# Instigator2012ConnectorSch.net
KiCad netlist of a schematic drawn in Altium Designer
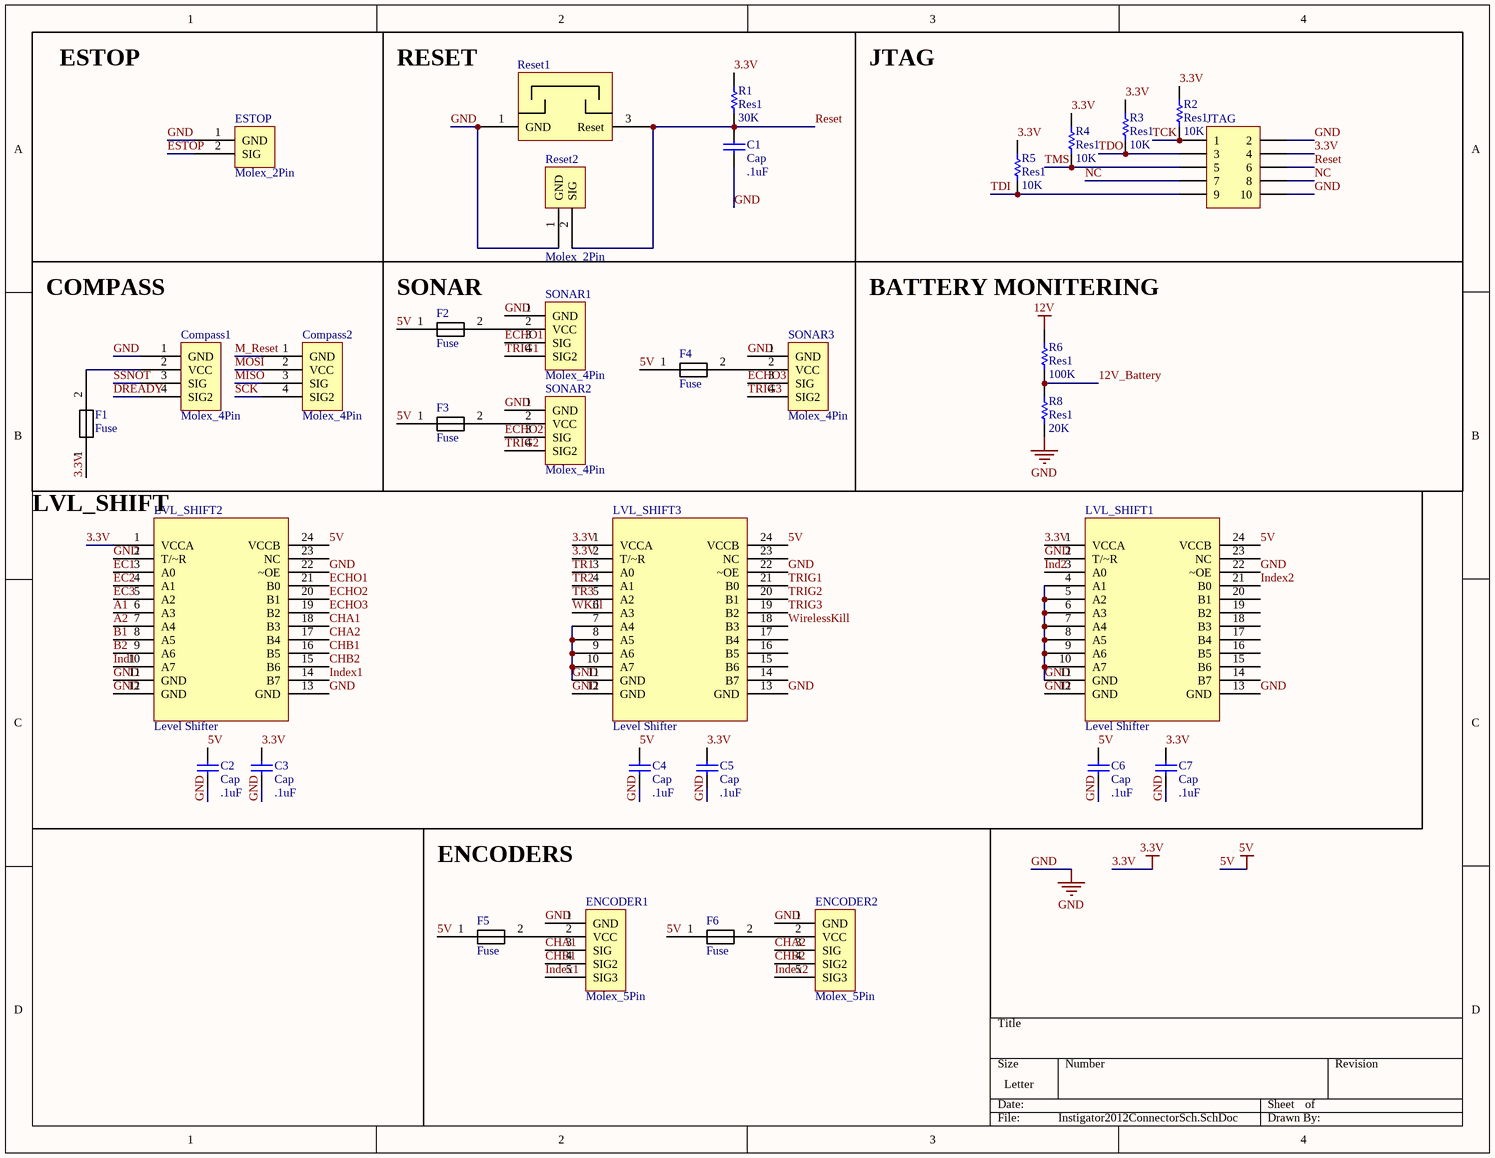
[diagram p0: Instigator2012ConnectorSch.SchDoc]

(export (version "E")
  (design (tool "Eeschema 10.0.6"))
  (components
    (comp (ref "C1")
      (value "Cap")
      (footprint "1608[0603]")
      (description "Capacitor")
      (fields (field (name "ALTIUM_VALUE") ".1uF") (field (name "PUBLISHER") "Altium Limited"))
      (libsource (lib "Miscellaneous Devices") (part "Cap"))
    )
    (comp (ref "C2")
      (value "Cap")
      (footprint "1608[0603]")
      (description "Capacitor")
      (fields (field (name "ALTIUM_VALUE") ".1uF") (field (name "PUBLISHER") "Altium Limited"))
      (libsource (lib "Miscellaneous Devices") (part "Cap"))
    )
    (comp (ref "C3")
      (value "Cap")
      (footprint "1608[0603]")
      (description "Capacitor")
      (fields (field (name "ALTIUM_VALUE") ".1uF") (field (name "PUBLISHER") "Altium Limited"))
      (libsource (lib "Miscellaneous Devices") (part "Cap"))
    )
    (comp (ref "C4")
      (value "Cap")
      (footprint "1608[0603]")
      (description "Capacitor")
      (fields (field (name "ALTIUM_VALUE") ".1uF") (field (name "PUBLISHER") "Altium Limited"))
      (libsource (lib "Miscellaneous Devices") (part "Cap"))
    )
    (comp (ref "C5")
      (value "Cap")
      (footprint "1608[0603]")
      (description "Capacitor")
      (fields (field (name "ALTIUM_VALUE") ".1uF") (field (name "PUBLISHER") "Altium Limited"))
      (libsource (lib "Miscellaneous Devices") (part "Cap"))
    )
    (comp (ref "C6")
      (value "Cap")
      (footprint "1608[0603]")
      (description "Capacitor")
      (fields (field (name "ALTIUM_VALUE") ".1uF") (field (name "PUBLISHER") "Altium Limited"))
      (libsource (lib "Miscellaneous Devices") (part "Cap"))
    )
    (comp (ref "C7")
      (value "Cap")
      (footprint "1608[0603]")
      (description "Capacitor")
      (fields (field (name "ALTIUM_VALUE") ".1uF") (field (name "PUBLISHER") "Altium Limited"))
      (libsource (lib "Miscellaneous Devices") (part "Cap"))
    )
    (comp (ref "Compass1")
      (value "Molex_4Pin")
      (footprint "PCBComponent_1")
      (libsource (lib "Molex_4Pin") (part "Molex_4Pin"))
    )
    (comp (ref "Compass2")
      (value "Molex_4Pin")
      (footprint "PCBComponent_1")
      (libsource (lib "Molex_4Pin") (part "Molex_4Pin"))
    )
    (comp (ref "ENCODER1")
      (value "Molex_5Pin")
      (footprint "PCBComponent_1")
      (libsource (lib "Molex_5Pin") (part "Molex_5Pin"))
    )
    (comp (ref "ENCODER2")
      (value "Molex_5Pin")
      (footprint "PCBComponent_1")
      (libsource (lib "Molex_5Pin") (part "Molex_5Pin"))
    )
    (comp (ref "ESTOP")
      (value "Molex_2Pin")
      (footprint "PCBComponent_1")
      (libsource (lib "") (part "Molex_2Pin_1"))
    )
    (comp (ref "F1")
      (value "Fuse")
      (footprint "PCBComponent_1 - duplicate")
      (libsource (lib "VPOL5A_PowerRegulator") (part "Fuse"))
    )
    (comp (ref "F2")
      (value "Fuse")
      (footprint "PCBComponent_1 - duplicate")
      (libsource (lib "VPOL5A_PowerRegulator") (part "Fuse"))
    )
    (comp (ref "F3")
      (value "Fuse")
      (footprint "PCBComponent_1 - duplicate")
      (libsource (lib "VPOL5A_PowerRegulator") (part "Fuse"))
    )
    (comp (ref "F4")
      (value "Fuse")
      (footprint "PCBComponent_1 - duplicate")
      (libsource (lib "VPOL5A_PowerRegulator") (part "Fuse"))
    )
    (comp (ref "F5")
      (value "Fuse")
      (footprint "PCBComponent_1 - duplicate")
      (libsource (lib "VPOL5A_PowerRegulator") (part "Fuse"))
    )
    (comp (ref "F6")
      (value "Fuse")
      (footprint "PCBComponent_1 - duplicate")
      (libsource (lib "VPOL5A_PowerRegulator") (part "Fuse"))
    )
    (comp (ref "JTAG")
      (value "Header 5X2")
      (footprint "HDR2X5")
      (description "Header, 5-Pin, Dual row")
      (fields (field (name "PUBLISHER") "Altium Limited"))
      (libsource (lib "Miscellaneous Connectors") (part "Header 5X2"))
    )
    (comp (ref "LVL_SHIFT1")
      (value "Level Shifter")
      (footprint "TSOP65P640X110-24N")
      (libsource (lib "LevelShifter_FairchildSemi") (part "Level Shifter"))
    )
    (comp (ref "LVL_SHIFT2")
      (value "Level Shifter")
      (footprint "TSOP65P640X110-24N")
      (libsource (lib "LevelShifter_FairchildSemi") (part "Level Shifter"))
    )
    (comp (ref "LVL_SHIFT3")
      (value "Level Shifter")
      (footprint "TSOP65P640X110-24N")
      (libsource (lib "LevelShifter_FairchildSemi") (part "Level Shifter"))
    )
    (comp (ref "R1")
      (value "Res1")
      (footprint "1608[0603]")
      (description "Resistor")
      (fields (field (name "ALTIUM_VALUE") "30K") (field (name "PUBLISHER") "Altium Limited"))
      (libsource (lib "Miscellaneous Devices") (part "Res1"))
    )
    (comp (ref "R2")
      (value "Res1")
      (footprint "1608[0603]")
      (description "Resistor")
      (fields (field (name "ALTIUM_VALUE") "10K") (field (name "PUBLISHER") "Altium Limited"))
      (libsource (lib "Miscellaneous Devices") (part "Res1"))
    )
    (comp (ref "R3")
      (value "Res1")
      (footprint "1608[0603]")
      (description "Resistor")
      (fields (field (name "ALTIUM_VALUE") "10K") (field (name "PUBLISHER") "Altium Limited"))
      (libsource (lib "Miscellaneous Devices") (part "Res1"))
    )
    (comp (ref "R4")
      (value "Res1")
      (footprint "1608[0603]")
      (description "Resistor")
      (fields (field (name "ALTIUM_VALUE") "10K") (field (name "PUBLISHER") "Altium Limited"))
      (libsource (lib "Miscellaneous Devices") (part "Res1"))
    )
    (comp (ref "R5")
      (value "Res1")
      (footprint "1608[0603]")
      (description "Resistor")
      (fields (field (name "ALTIUM_VALUE") "10K") (field (name "PUBLISHER") "Altium Limited"))
      (libsource (lib "Miscellaneous Devices") (part "Res1"))
    )
    (comp (ref "R6")
      (value "Res1")
      (footprint "1608[0603]")
      (description "Resistor")
      (fields (field (name "ALTIUM_VALUE") "100K") (field (name "PUBLISHER") "Altium Limited"))
      (libsource (lib "Miscellaneous Devices") (part "Res1"))
    )
    (comp (ref "R8")
      (value "Res1")
      (footprint "1608[0603]")
      (description "Resistor")
      (fields (field (name "ALTIUM_VALUE") "20K") (field (name "PUBLISHER") "Altium Limited"))
      (libsource (lib "Miscellaneous Devices") (part "Res1"))
    )
    (comp (ref "Reset1")
      (value "l")
      (footprint "PCBComponent_1")
      (libsource (lib "PushButton_Reset") (part "Component_1"))
    )
    (comp (ref "Reset2")
      (value "Molex_2Pin")
      (footprint "PCBComponent_1")
      (libsource (lib "Molex_2Pin") (part "Molex_2Pin"))
    )
    (comp (ref "SONAR1")
      (value "Molex_4Pin")
      (footprint "PCBComponent_1")
      (libsource (lib "Molex_4Pin") (part "Molex_4Pin"))
    )
    (comp (ref "SONAR2")
      (value "Molex_4Pin")
      (footprint "PCBComponent_1")
      (libsource (lib "Molex_4Pin") (part "Molex_4Pin"))
    )
    (comp (ref "SONAR3")
      (value "Molex_4Pin")
      (footprint "PCBComponent_1")
      (libsource (lib "Molex_4Pin") (part "Molex_4Pin"))
    )
  )
  (nets
    (net (code "1") (name "/12V_Battery") (class "Default")
      (node (ref "R6") (pin "1") (pinfunction "1_1") (pintype "passive"))
      (node (ref "R8") (pin "2") (pinfunction "2_2") (pintype "passive"))
    )
    (net (code "2") (name "/A1") (class "Default")
      (node (ref "LVL_SHIFT2") (pin "6") (pinfunction "A3_6") (pintype "passive"))
    )
    (net (code "3") (name "/A2") (class "Default")
      (node (ref "LVL_SHIFT2") (pin "7") (pinfunction "A4_7") (pintype "passive"))
    )
    (net (code "4") (name "/B1") (class "Default")
      (node (ref "LVL_SHIFT2") (pin "8") (pinfunction "A5_8") (pintype "passive"))
    )
    (net (code "5") (name "/B2") (class "Default")
      (node (ref "LVL_SHIFT2") (pin "9") (pinfunction "A6_9") (pintype "passive"))
    )
    (net (code "6") (name "/CHA1") (class "Default")
      (node (ref "ENCODER1") (pin "3") (pinfunction "SIG_3") (pintype "power_in"))
      (node (ref "LVL_SHIFT2") (pin "18") (pinfunction "B3_18") (pintype "passive"))
    )
    (net (code "7") (name "/CHA2") (class "Default")
      (node (ref "ENCODER2") (pin "3") (pinfunction "SIG_3") (pintype "power_in"))
      (node (ref "LVL_SHIFT2") (pin "17") (pinfunction "B4_17") (pintype "passive"))
    )
    (net (code "8") (name "/CHB1") (class "Default")
      (node (ref "ENCODER1") (pin "4") (pinfunction "SIG2_4") (pintype "power_in"))
      (node (ref "LVL_SHIFT2") (pin "16") (pinfunction "B5_16") (pintype "passive"))
    )
    (net (code "9") (name "/CHB2") (class "Default")
      (node (ref "ENCODER2") (pin "4") (pinfunction "SIG2_4") (pintype "power_in"))
      (node (ref "LVL_SHIFT2") (pin "15") (pinfunction "B6_15") (pintype "passive"))
    )
    (net (code "10") (name "/DREADY") (class "Default")
      (node (ref "Compass1") (pin "4") (pinfunction "SIG2_4") (pintype "power_in"))
    )
    (net (code "11") (name "/EC1") (class "Default")
      (node (ref "LVL_SHIFT2") (pin "3") (pinfunction "A0_3") (pintype "passive"))
    )
    (net (code "12") (name "/EC2") (class "Default")
      (node (ref "LVL_SHIFT2") (pin "4") (pinfunction "A1_4") (pintype "passive"))
    )
    (net (code "13") (name "/EC3") (class "Default")
      (node (ref "LVL_SHIFT2") (pin "5") (pinfunction "A2_5") (pintype "passive"))
    )
    (net (code "14") (name "/ECHO1") (class "Default")
      (node (ref "LVL_SHIFT2") (pin "21") (pinfunction "B0_21") (pintype "passive"))
      (node (ref "SONAR1") (pin "3") (pinfunction "SIG_3") (pintype "power_in"))
    )
    (net (code "15") (name "/ECHO2") (class "Default")
      (node (ref "LVL_SHIFT2") (pin "20") (pinfunction "B1_20") (pintype "passive"))
      (node (ref "SONAR2") (pin "3") (pinfunction "SIG_3") (pintype "power_in"))
    )
    (net (code "16") (name "/ECHO3") (class "Default")
      (node (ref "LVL_SHIFT2") (pin "19") (pinfunction "B2_19") (pintype "passive"))
      (node (ref "SONAR3") (pin "3") (pinfunction "SIG_3") (pintype "power_in"))
    )
    (net (code "17") (name "/ESTOP") (class "Default")
      (node (ref "ESTOP") (pin "2") (pinfunction "SIG_2") (pintype "passive"))
    )
    (net (code "18") (name "/Ind1") (class "Default")
      (node (ref "LVL_SHIFT2") (pin "10") (pinfunction "A7_10") (pintype "passive"))
    )
    (net (code "19") (name "/Ind2") (class "Default")
      (node (ref "LVL_SHIFT1") (pin "3") (pinfunction "A0_3") (pintype "passive"))
    )
    (net (code "20") (name "/Index1") (class "Default")
      (node (ref "ENCODER1") (pin "5") (pinfunction "SIG3_5") (pintype "power_in"))
      (node (ref "LVL_SHIFT2") (pin "14") (pinfunction "B7_14") (pintype "passive"))
    )
    (net (code "21") (name "/Index2") (class "Default")
      (node (ref "ENCODER2") (pin "5") (pinfunction "SIG3_5") (pintype "power_in"))
      (node (ref "LVL_SHIFT1") (pin "21") (pinfunction "B0_21") (pintype "passive"))
    )
    (net (code "22") (name "/MISO") (class "Default")
      (node (ref "Compass2") (pin "3") (pinfunction "SIG_3") (pintype "power_in"))
    )
    (net (code "23") (name "/MOSI") (class "Default")
      (node (ref "Compass2") (pin "2") (pinfunction "VCC_2") (pintype "power_in"))
    )
    (net (code "24") (name "/M_Reset") (class "Default")
      (node (ref "Compass2") (pin "1") (pinfunction "GND_1") (pintype "power_in"))
    )
    (net (code "25") (name "/NC") (class "Default")
      (node (ref "JTAG") (pin "7") (pinfunction "7_7") (pintype "passive"))
      (node (ref "JTAG") (pin "8") (pinfunction "8_8") (pintype "passive"))
    )
    (net (code "26") (name "/Reset") (class "Default")
      (node (ref "C1") (pin "2") (pinfunction "2_2") (pintype "passive"))
      (node (ref "JTAG") (pin "6") (pinfunction "6_6") (pintype "passive"))
      (node (ref "R1") (pin "1") (pinfunction "1_1") (pintype "passive"))
      (node (ref "Reset1") (pin "3") (pinfunction "Reset_3") (pintype "passive"))
      (node (ref "Reset2") (pin "2") (pinfunction "SIG_2") (pintype "passive"))
    )
    (net (code "27") (name "/SCK") (class "Default")
      (node (ref "Compass2") (pin "4") (pinfunction "SIG2_4") (pintype "power_in"))
    )
    (net (code "28") (name "/SSNOT") (class "Default")
      (node (ref "Compass1") (pin "3") (pinfunction "SIG_3") (pintype "power_in"))
    )
    (net (code "29") (name "/TCK") (class "Default")
      (node (ref "JTAG") (pin "1") (pinfunction "1_1") (pintype "passive"))
      (node (ref "R2") (pin "1") (pinfunction "1_1") (pintype "passive"))
    )
    (net (code "30") (name "/TDI") (class "Default")
      (node (ref "JTAG") (pin "9") (pinfunction "9_9") (pintype "passive"))
      (node (ref "R5") (pin "1") (pinfunction "1_1") (pintype "passive"))
    )
    (net (code "31") (name "/TDO") (class "Default")
      (node (ref "JTAG") (pin "3") (pinfunction "3_3") (pintype "passive"))
      (node (ref "R3") (pin "1") (pinfunction "1_1") (pintype "passive"))
    )
    (net (code "32") (name "/TMS") (class "Default")
      (node (ref "JTAG") (pin "5") (pinfunction "5_5") (pintype "passive"))
      (node (ref "R4") (pin "1") (pinfunction "1_1") (pintype "passive"))
    )
    (net (code "33") (name "/TR1") (class "Default")
      (node (ref "LVL_SHIFT3") (pin "3") (pinfunction "A0_3") (pintype "passive"))
    )
    (net (code "34") (name "/TR2") (class "Default")
      (node (ref "LVL_SHIFT3") (pin "4") (pinfunction "A1_4") (pintype "passive"))
    )
    (net (code "35") (name "/TR3") (class "Default")
      (node (ref "LVL_SHIFT3") (pin "5") (pinfunction "A2_5") (pintype "passive"))
    )
    (net (code "36") (name "/TRIG1") (class "Default")
      (node (ref "LVL_SHIFT3") (pin "21") (pinfunction "B0_21") (pintype "passive"))
      (node (ref "SONAR1") (pin "4") (pinfunction "SIG2_4") (pintype "power_in"))
    )
    (net (code "37") (name "/TRIG2") (class "Default")
      (node (ref "LVL_SHIFT3") (pin "20") (pinfunction "B1_20") (pintype "passive"))
      (node (ref "SONAR2") (pin "4") (pinfunction "SIG2_4") (pintype "power_in"))
    )
    (net (code "38") (name "/TRIG3") (class "Default")
      (node (ref "LVL_SHIFT3") (pin "19") (pinfunction "B2_19") (pintype "passive"))
      (node (ref "SONAR3") (pin "4") (pinfunction "SIG2_4") (pintype "power_in"))
    )
    (net (code "39") (name "/WKill") (class "Default")
      (node (ref "LVL_SHIFT3") (pin "6") (pinfunction "A3_6") (pintype "passive"))
    )
    (net (code "40") (name "/WirelessKill") (class "Default")
      (node (ref "LVL_SHIFT3") (pin "18") (pinfunction "B3_18") (pintype "passive"))
    )
    (net (code "41") (name "3.3V") (class "Default")
      (node (ref "C3") (pin "2") (pinfunction "2_2") (pintype "passive"))
      (node (ref "C5") (pin "2") (pinfunction "2_2") (pintype "passive"))
      (node (ref "C7") (pin "2") (pinfunction "2_2") (pintype "passive"))
      (node (ref "F1") (pin "1") (pintype "passive"))
      (node (ref "JTAG") (pin "4") (pinfunction "4_4") (pintype "passive"))
      (node (ref "LVL_SHIFT1") (pin "1") (pinfunction "VCCA_1") (pintype "power_in"))
      (node (ref "LVL_SHIFT2") (pin "1") (pinfunction "VCCA_1") (pintype "power_in"))
      (node (ref "LVL_SHIFT3") (pin "1") (pinfunction "VCCA_1") (pintype "power_in"))
      (node (ref "LVL_SHIFT3") (pin "2") (pinfunction "T/~R_2") (pintype "passive"))
      (node (ref "R1") (pin "2") (pinfunction "2_2") (pintype "passive"))
      (node (ref "R2") (pin "2") (pinfunction "2_2") (pintype "passive"))
      (node (ref "R3") (pin "2") (pinfunction "2_2") (pintype "passive"))
      (node (ref "R4") (pin "2") (pinfunction "2_2") (pintype "passive"))
      (node (ref "R5") (pin "2") (pinfunction "2_2") (pintype "passive"))
    )
    (net (code "42") (name "5V") (class "Default")
      (node (ref "C2") (pin "2") (pinfunction "2_2") (pintype "passive"))
      (node (ref "C4") (pin "2") (pinfunction "2_2") (pintype "passive"))
      (node (ref "C6") (pin "2") (pinfunction "2_2") (pintype "passive"))
      (node (ref "F2") (pin "1") (pintype "passive"))
      (node (ref "F3") (pin "1") (pintype "passive"))
      (node (ref "F4") (pin "1") (pintype "passive"))
      (node (ref "F5") (pin "1") (pintype "passive"))
      (node (ref "F6") (pin "1") (pintype "passive"))
      (node (ref "LVL_SHIFT1") (pin "24") (pinfunction "VCCB_24") (pintype "passive"))
      (node (ref "LVL_SHIFT2") (pin "24") (pinfunction "VCCB_24") (pintype "passive"))
      (node (ref "LVL_SHIFT3") (pin "24") (pinfunction "VCCB_24") (pintype "passive"))
    )
    (net (code "43") (name "12V") (class "Default")
      (node (ref "R6") (pin "2") (pinfunction "2_2") (pintype "passive"))
    )
    (net (code "44") (name "GND") (class "Default")
      (node (ref "C1") (pin "1") (pinfunction "1_1") (pintype "passive"))
      (node (ref "C2") (pin "1") (pinfunction "1_1") (pintype "passive"))
      (node (ref "C3") (pin "1") (pinfunction "1_1") (pintype "passive"))
      (node (ref "C4") (pin "1") (pinfunction "1_1") (pintype "passive"))
      (node (ref "C5") (pin "1") (pinfunction "1_1") (pintype "passive"))
      (node (ref "C6") (pin "1") (pinfunction "1_1") (pintype "passive"))
      (node (ref "C7") (pin "1") (pinfunction "1_1") (pintype "passive"))
      (node (ref "Compass1") (pin "1") (pinfunction "GND_1") (pintype "power_in"))
      (node (ref "ENCODER1") (pin "1") (pinfunction "GND_1") (pintype "power_in"))
      (node (ref "ENCODER2") (pin "1") (pinfunction "GND_1") (pintype "power_in"))
      (node (ref "ESTOP") (pin "1") (pinfunction "GND_1") (pintype "power_in"))
      (node (ref "JTAG") (pin "10") (pinfunction "10_10") (pintype "passive"))
      (node (ref "JTAG") (pin "2") (pinfunction "2_2") (pintype "passive"))
      (node (ref "LVL_SHIFT1") (pin "10") (pinfunction "A7_10") (pintype "passive"))
      (node (ref "LVL_SHIFT1") (pin "11") (pinfunction "GND_11") (pintype "passive"))
      (node (ref "LVL_SHIFT1") (pin "12") (pinfunction "GND_12") (pintype "passive"))
      (node (ref "LVL_SHIFT1") (pin "13") (pinfunction "GND_13") (pintype "passive"))
      (node (ref "LVL_SHIFT1") (pin "2") (pinfunction "T/~R_2") (pintype "passive"))
      (node (ref "LVL_SHIFT1") (pin "22") (pinfunction "~OE_22") (pintype "passive"))
      (node (ref "LVL_SHIFT1") (pin "4") (pinfunction "A1_4") (pintype "passive"))
      (node (ref "LVL_SHIFT1") (pin "5") (pinfunction "A2_5") (pintype "passive"))
      (node (ref "LVL_SHIFT1") (pin "6") (pinfunction "A3_6") (pintype "passive"))
      (node (ref "LVL_SHIFT1") (pin "7") (pinfunction "A4_7") (pintype "passive"))
      (node (ref "LVL_SHIFT1") (pin "8") (pinfunction "A5_8") (pintype "passive"))
      (node (ref "LVL_SHIFT1") (pin "9") (pinfunction "A6_9") (pintype "passive"))
      (node (ref "LVL_SHIFT2") (pin "11") (pinfunction "GND_11") (pintype "passive"))
      (node (ref "LVL_SHIFT2") (pin "12") (pinfunction "GND_12") (pintype "passive"))
      (node (ref "LVL_SHIFT2") (pin "13") (pinfunction "GND_13") (pintype "passive"))
      (node (ref "LVL_SHIFT2") (pin "2") (pinfunction "T/~R_2") (pintype "passive"))
      (node (ref "LVL_SHIFT2") (pin "22") (pinfunction "~OE_22") (pintype "passive"))
      (node (ref "LVL_SHIFT3") (pin "10") (pinfunction "A7_10") (pintype "passive"))
      (node (ref "LVL_SHIFT3") (pin "11") (pinfunction "GND_11") (pintype "passive"))
      (node (ref "LVL_SHIFT3") (pin "12") (pinfunction "GND_12") (pintype "passive"))
      (node (ref "LVL_SHIFT3") (pin "13") (pinfunction "GND_13") (pintype "passive"))
      (node (ref "LVL_SHIFT3") (pin "22") (pinfunction "~OE_22") (pintype "passive"))
      (node (ref "LVL_SHIFT3") (pin "7") (pinfunction "A4_7") (pintype "passive"))
      (node (ref "LVL_SHIFT3") (pin "8") (pinfunction "A5_8") (pintype "passive"))
      (node (ref "LVL_SHIFT3") (pin "9") (pinfunction "A6_9") (pintype "passive"))
      (node (ref "R8") (pin "1") (pinfunction "1_1") (pintype "passive"))
      (node (ref "Reset1") (pin "1") (pinfunction "GND_1") (pintype "power_in"))
      (node (ref "Reset2") (pin "1") (pinfunction "GND_1") (pintype "power_in"))
      (node (ref "SONAR1") (pin "1") (pinfunction "GND_1") (pintype "power_in"))
      (node (ref "SONAR2") (pin "1") (pinfunction "GND_1") (pintype "power_in"))
      (node (ref "SONAR3") (pin "1") (pinfunction "GND_1") (pintype "power_in"))
    )
    (net (code "45") (name "Net-(Compass1-VCC)") (class "Default")
      (node (ref "Compass1") (pin "2") (pinfunction "VCC_2") (pintype "power_in"))
      (node (ref "F1") (pin "2") (pintype "passive"))
    )
    (net (code "46") (name "Net-(ENCODER1-VCC)") (class "Default")
      (node (ref "ENCODER1") (pin "2") (pinfunction "VCC_2") (pintype "power_in"))
      (node (ref "F5") (pin "2") (pintype "passive"))
    )
    (net (code "47") (name "Net-(ENCODER2-VCC)") (class "Default")
      (node (ref "ENCODER2") (pin "2") (pinfunction "VCC_2") (pintype "power_in"))
      (node (ref "F6") (pin "2") (pintype "passive"))
    )
    (net (code "48") (name "Net-(SONAR1-VCC)") (class "Default")
      (node (ref "F2") (pin "2") (pintype "passive"))
      (node (ref "SONAR1") (pin "2") (pinfunction "VCC_2") (pintype "power_in"))
    )
    (net (code "49") (name "Net-(SONAR2-VCC)") (class "Default")
      (node (ref "F3") (pin "2") (pintype "passive"))
      (node (ref "SONAR2") (pin "2") (pinfunction "VCC_2") (pintype "power_in"))
    )
    (net (code "50") (name "Net-(SONAR3-VCC)") (class "Default")
      (node (ref "F4") (pin "2") (pintype "passive"))
      (node (ref "SONAR3") (pin "2") (pinfunction "VCC_2") (pintype "power_in"))
    )
    (net (code "51") (name "unconnected-(LVL_SHIFT1-B1-Pad20)") (class "Default")
      (node (ref "LVL_SHIFT1") (pin "20") (pinfunction "B1_20") (pintype "passive"))
    )
    (net (code "52") (name "unconnected-(LVL_SHIFT1-B2-Pad19)") (class "Default")
      (node (ref "LVL_SHIFT1") (pin "19") (pinfunction "B2_19") (pintype "passive"))
    )
    (net (code "53") (name "unconnected-(LVL_SHIFT1-B3-Pad18)") (class "Default")
      (node (ref "LVL_SHIFT1") (pin "18") (pinfunction "B3_18") (pintype "passive"))
    )
    (net (code "54") (name "unconnected-(LVL_SHIFT1-B4-Pad17)") (class "Default")
      (node (ref "LVL_SHIFT1") (pin "17") (pinfunction "B4_17") (pintype "passive"))
    )
    (net (code "55") (name "unconnected-(LVL_SHIFT1-B5-Pad16)") (class "Default")
      (node (ref "LVL_SHIFT1") (pin "16") (pinfunction "B5_16") (pintype "passive"))
    )
    (net (code "56") (name "unconnected-(LVL_SHIFT1-B6-Pad15)") (class "Default")
      (node (ref "LVL_SHIFT1") (pin "15") (pinfunction "B6_15") (pintype "passive"))
    )
    (net (code "57") (name "unconnected-(LVL_SHIFT1-B7-Pad14)") (class "Default")
      (node (ref "LVL_SHIFT1") (pin "14") (pinfunction "B7_14") (pintype "passive"))
    )
    (net (code "58") (name "unconnected-(LVL_SHIFT1-NC-Pad23)") (class "Default")
      (node (ref "LVL_SHIFT1") (pin "23") (pinfunction "NC_23") (pintype "passive"))
    )
    (net (code "59") (name "unconnected-(LVL_SHIFT2-NC-Pad23)") (class "Default")
      (node (ref "LVL_SHIFT2") (pin "23") (pinfunction "NC_23") (pintype "passive"))
    )
    (net (code "60") (name "unconnected-(LVL_SHIFT3-B4-Pad17)") (class "Default")
      (node (ref "LVL_SHIFT3") (pin "17") (pinfunction "B4_17") (pintype "passive"))
    )
    (net (code "61") (name "unconnected-(LVL_SHIFT3-B5-Pad16)") (class "Default")
      (node (ref "LVL_SHIFT3") (pin "16") (pinfunction "B5_16") (pintype "passive"))
    )
    (net (code "62") (name "unconnected-(LVL_SHIFT3-B6-Pad15)") (class "Default")
      (node (ref "LVL_SHIFT3") (pin "15") (pinfunction "B6_15") (pintype "passive"))
    )
    (net (code "63") (name "unconnected-(LVL_SHIFT3-B7-Pad14)") (class "Default")
      (node (ref "LVL_SHIFT3") (pin "14") (pinfunction "B7_14") (pintype "passive"))
    )
    (net (code "64") (name "unconnected-(LVL_SHIFT3-NC-Pad23)") (class "Default")
      (node (ref "LVL_SHIFT3") (pin "23") (pinfunction "NC_23") (pintype "passive"))
    )
  )
)
